# Input_1.net
KiCad netlist of a schematic drawn in Altium Designer
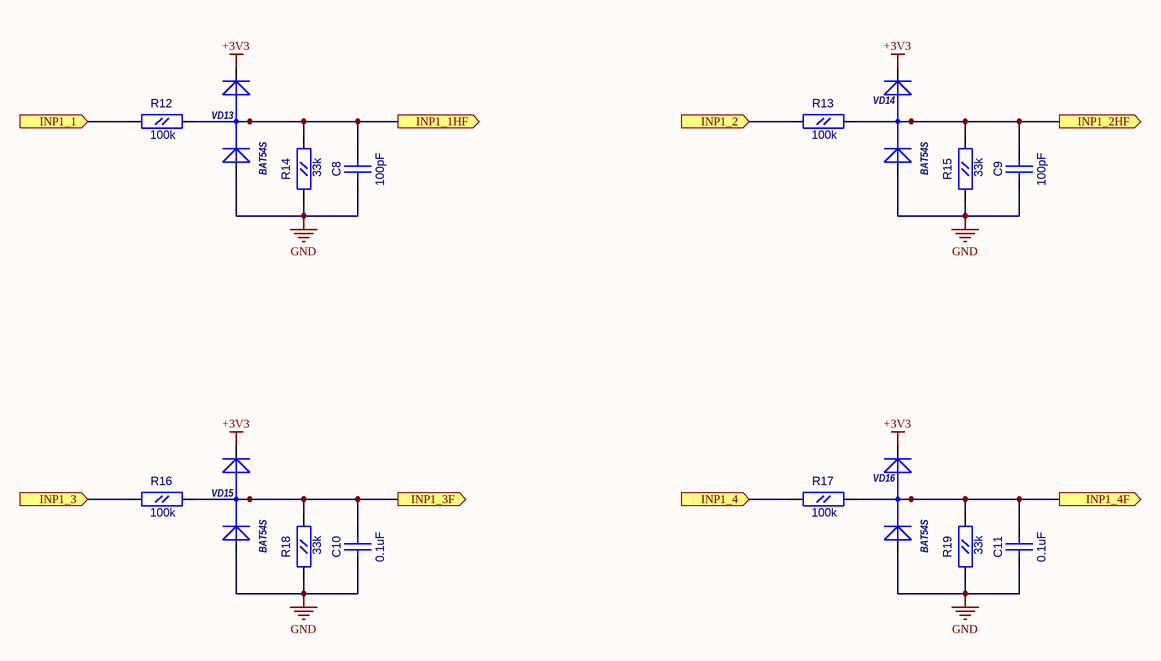
[diagram p0: Input_1.SchDoc]

(export (version "E")
  (design (tool "Eeschema 10.0.6"))
  (components
    (comp (ref "C8")
      (value "100pF")
      (footprint "CC0603")
      (description "CC0603")
      (libsource (lib "gprs_modem_2") (part "CC0603"))
    )
    (comp (ref "C9")
      (value "100pF")
      (footprint "CC0603")
      (description "CC0603")
      (libsource (lib "gprs_modem_2") (part "CC0603"))
    )
    (comp (ref "C10")
      (value "0.1uF")
      (footprint "CC0603")
      (description "CC0603")
      (libsource (lib "gprs_modem_2") (part "CC0603"))
    )
    (comp (ref "C11")
      (value "0.1uF")
      (footprint "CC0603")
      (description "CC0603")
      (libsource (lib "gprs_modem_2") (part "CC0603"))
    )
    (comp (ref "R12")
      (value "100k")
      (footprint "RC0603")
      (description "RC0603")
      (libsource (lib "gprs_modem_2") (part "RC0603"))
    )
    (comp (ref "R13")
      (value "100k")
      (footprint "RC0603")
      (description "RC0603")
      (libsource (lib "gprs_modem_2") (part "RC0603"))
    )
    (comp (ref "R14")
      (value "33k")
      (footprint "RC0603")
      (description "RC0603")
      (libsource (lib "gprs_modem_2") (part "RC0603"))
    )
    (comp (ref "R15")
      (value "33k")
      (footprint "RC0603")
      (description "RC0603")
      (libsource (lib "gprs_modem_2") (part "RC0603"))
    )
    (comp (ref "R16")
      (value "100k")
      (footprint "RC0603")
      (description "RC0603")
      (libsource (lib "gprs_modem_2") (part "RC0603"))
    )
    (comp (ref "R17")
      (value "100k")
      (footprint "RC0603")
      (description "RC0603")
      (libsource (lib "gprs_modem_2") (part "RC0603"))
    )
    (comp (ref "R18")
      (value "33k")
      (footprint "RC0603")
      (description "RC0603")
      (libsource (lib "gprs_modem_2") (part "RC0603"))
    )
    (comp (ref "R19")
      (value "33k")
      (footprint "RC0603")
      (description "RC0603")
      (libsource (lib "gprs_modem_2") (part "RC0603"))
    )
    (comp (ref "VD13")
      (value "BAT54S")
      (footprint "SOT-23(GSD)")
      (description "1.0 Ampere General Purpose Rectifier")
      (libsource (lib "gprs_modem_2") (part "BAT54S"))
    )
    (comp (ref "VD14")
      (value "BAT54S")
      (footprint "SOT-23(GSD)")
      (description "1.0 Ampere General Purpose Rectifier")
      (libsource (lib "gprs_modem_2") (part "BAT54S"))
    )
    (comp (ref "VD15")
      (value "BAT54S")
      (footprint "SOT-23(GSD)")
      (description "1.0 Ampere General Purpose Rectifier")
      (libsource (lib "gprs_modem_2") (part "BAT54S"))
    )
    (comp (ref "VD16")
      (value "BAT54S")
      (footprint "SOT-23(GSD)")
      (description "1.0 Ampere General Purpose Rectifier")
      (libsource (lib "gprs_modem_2") (part "BAT54S"))
    )
  )
  (nets
    (net (code "1") (name "+3V3") (class "Default")
      (node (ref "VD13") (pin "2") (pinfunction "K_2") (pintype "passive"))
      (node (ref "VD14") (pin "2") (pinfunction "K_2") (pintype "passive"))
      (node (ref "VD15") (pin "2") (pinfunction "K_2") (pintype "passive"))
      (node (ref "VD16") (pin "2") (pinfunction "K_2") (pintype "passive"))
    )
    (net (code "2") (name "/INP1_1") (class "Default")
      (node (ref "R12") (pin "1") (pinfunction "A_1") (pintype "passive"))
    )
    (net (code "3") (name "/INP1_1HF") (class "Default")
      (node (ref "C8") (pin "2") (pinfunction "B_2") (pintype "passive"))
      (node (ref "R12") (pin "2") (pinfunction "B_2") (pintype "passive"))
      (node (ref "R14") (pin "2") (pinfunction "B_2") (pintype "passive"))
      (node (ref "VD13") (pin "3") (pinfunction "AK_3") (pintype "passive"))
    )
    (net (code "4") (name "/INP1_2") (class "Default")
      (node (ref "R13") (pin "1") (pinfunction "A_1") (pintype "passive"))
    )
    (net (code "5") (name "/INP1_2HF") (class "Default")
      (node (ref "C9") (pin "2") (pinfunction "B_2") (pintype "passive"))
      (node (ref "R13") (pin "2") (pinfunction "B_2") (pintype "passive"))
      (node (ref "R15") (pin "2") (pinfunction "B_2") (pintype "passive"))
      (node (ref "VD14") (pin "3") (pinfunction "AK_3") (pintype "passive"))
    )
    (net (code "6") (name "/INP1_3") (class "Default")
      (node (ref "R16") (pin "1") (pinfunction "A_1") (pintype "passive"))
    )
    (net (code "7") (name "/INP1_3F") (class "Default")
      (node (ref "C10") (pin "2") (pinfunction "B_2") (pintype "passive"))
      (node (ref "R16") (pin "2") (pinfunction "B_2") (pintype "passive"))
      (node (ref "R18") (pin "2") (pinfunction "B_2") (pintype "passive"))
      (node (ref "VD15") (pin "3") (pinfunction "AK_3") (pintype "passive"))
    )
    (net (code "8") (name "/INP1_4") (class "Default")
      (node (ref "R17") (pin "1") (pinfunction "A_1") (pintype "passive"))
    )
    (net (code "9") (name "/INP1_4F") (class "Default")
      (node (ref "C11") (pin "2") (pinfunction "B_2") (pintype "passive"))
      (node (ref "R17") (pin "2") (pinfunction "B_2") (pintype "passive"))
      (node (ref "R19") (pin "2") (pinfunction "B_2") (pintype "passive"))
      (node (ref "VD16") (pin "3") (pinfunction "AK_3") (pintype "passive"))
    )
    (net (code "10") (name "GND") (class "Default")
      (node (ref "C10") (pin "1") (pinfunction "A_1") (pintype "passive"))
      (node (ref "C11") (pin "1") (pinfunction "A_1") (pintype "passive"))
      (node (ref "C8") (pin "1") (pinfunction "A_1") (pintype "passive"))
      (node (ref "C9") (pin "1") (pinfunction "A_1") (pintype "passive"))
      (node (ref "R14") (pin "1") (pinfunction "A_1") (pintype "passive"))
      (node (ref "R15") (pin "1") (pinfunction "A_1") (pintype "passive"))
      (node (ref "R18") (pin "1") (pinfunction "A_1") (pintype "passive"))
      (node (ref "R19") (pin "1") (pinfunction "A_1") (pintype "passive"))
      (node (ref "VD13") (pin "1") (pinfunction "A_1") (pintype "passive"))
      (node (ref "VD14") (pin "1") (pinfunction "A_1") (pintype "passive"))
      (node (ref "VD15") (pin "1") (pinfunction "A_1") (pintype "passive"))
      (node (ref "VD16") (pin "1") (pinfunction "A_1") (pintype "passive"))
    )
  )
)
